# driver1.net
KiCad netlist of a schematic drawn in Altium Designer
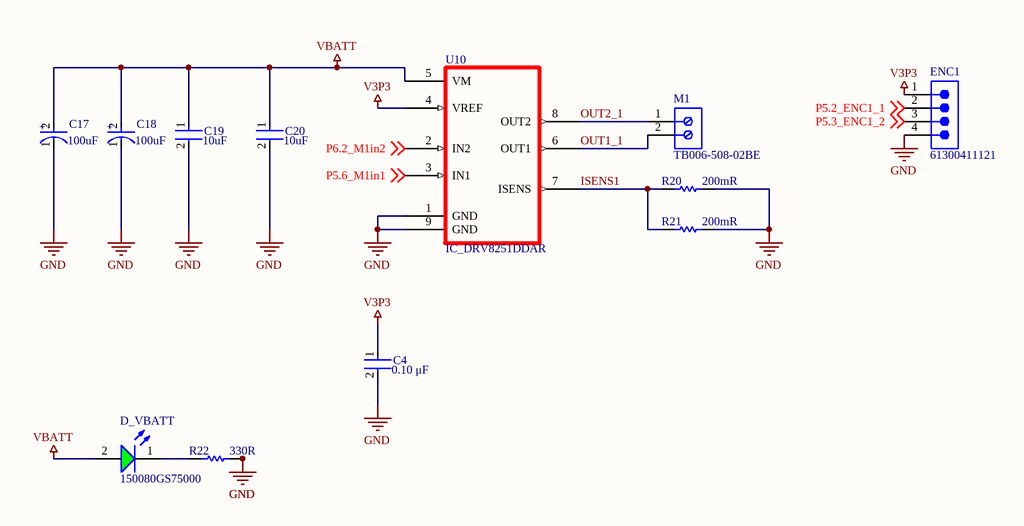
[diagram p0: driver1.SchDoc]

(export (version "E")
  (design (tool "Eeschema 10.0.6"))
  (components
    (comp (ref "C4")
      (value "C0805C104K5RACTU")
      (footprint "FP-C0805C-DN-MFG")
      (description "CAP CER 0.1UF 50V X7R 0805")
      (fields
        (field (name "MANUFACTURER") "KEMET")
        (field (name "OCTOPART") "https://octopart.com/c0805c104k5ractu-kemet-143926")
        (field (name "CAPACITANCE") "0.10 μF")
      )
      (libsource (lib "Altium Content Vault") (part "b4654b650e69147ec39a6b967a45e02"))
    )
    (comp (ref "C17")
      (value "100uF")
      (footprint "FP-SD8-MFG")
      (description "CAP ALUM 100UF 20% 25V SMD")
      (fields (field (name "VOLTAGE") "25V") (field (name "TOLERANCE") "20%"))
      (libsource (lib "Altium Content Vault") (part "a00bbbee19879c290e62620ae7e47b1"))
    )
    (comp (ref "C18")
      (value "100uF")
      (footprint "FP-SD8-MFG")
      (description "CAP ALUM 100UF 20% 25V SMD")
      (fields (field (name "VOLTAGE") "25V") (field (name "TOLERANCE") "20%"))
      (libsource (lib "Altium Content Vault") (part "a00bbbee19879c290e62620ae7e47b1"))
    )
    (comp (ref "C19")
      (value "10uF")
      (footprint "FP-C0805C-DG-MFG")
      (description "CAP CER 10UF 10V X5R 0805")
      (fields
        (field (name "MANUFACTURER") "KEMET")
        (field (name "MANUFACTURER PART NUMBER") "C0805C106K8PACTU")
      )
      (libsource (lib "Altium Content Vault") (part "11868f565c42a9108669ba33697ecf6"))
    )
    (comp (ref "C20")
      (value "10uF")
      (footprint "FP-C0805C-DG-MFG")
      (description "CAP CER 10UF 10V X5R 0805")
      (fields
        (field (name "MANUFACTURER") "KEMET")
        (field (name "MANUFACTURER PART NUMBER") "C0805C106K8PACTU")
      )
      (libsource (lib "Altium Content Vault") (part "11868f565c42a9108669ba33697ecf6"))
    )
    (comp (ref "D_VBATT")
      (value "150080GS75000")
      (footprint "WL-SMCW_0805_150080xx75000")
      (description "LED GREEN CLEAR 0805 SMD")
      (fields (field (name "MANUFACTURER") "Wurth Electronics"))
      (libsource (lib "Altium Content Vault") (part "LED_Green_2A-1K"))
    )
    (comp (ref "ENC1")
      (value "61300411121")
      (footprint "61300411121")
      (libsource (lib "Altium Content Vault") (part "Header_Male_1R_04P"))
    )
    (comp (ref "M1")
      (value "CONN_TB006_-508-02BE")
      (footprint "CUI_TB006 -508-02BE")
      (description "2~24 Poles, Screw Type, Horizontal, 5.08 Pitch, 26~14 (AWG), Terminal Block Connector")
      (fields
        (field (name "MF") "CUI Devices")
        (field (name "MP") "TB006 -508-02BE")
        (field (name "MANUFACTURER PART NUMBER") "TB006-508-02BE")
      )
      (libsource (lib "ECE453_S24") (part "CONN_TB006_-508-02BE"))
    )
    (comp (ref "R20")
      (value "200mR")
      (footprint "RESC2013X60X40LL20T25")
      (description "RES 0.2 OHM 1% 1/2W 0805")
      (fields
        (field (name "MANUFACTURER") "Panasonic")
        (field (name "MANUFACTURER PART NUMBER") "ERJ-6DSFR20V")
      )
      (libsource (lib "Altium Content Vault") (part "RES"))
    )
    (comp (ref "R21")
      (value "200mR")
      (footprint "RESC2013X60X40LL20T25")
      (description "RES 0.2 OHM 1% 1/2W 0805")
      (fields
        (field (name "MANUFACTURER") "Panasonic")
        (field (name "MANUFACTURER PART NUMBER") "ERJ-6DSFR20V")
      )
      (libsource (lib "Altium Content Vault") (part "RES"))
    )
    (comp (ref "R22")
      (value "330R")
      (footprint "RESC2013X60X40LL20T25")
      (description "RES SMD 330 OHM 1% 1/8W 0805")
      (fields
        (field (name "MANUFACTURER") "Panasonic")
        (field (name "MANUFACTURER PART NUMBER") "ERJ-6ENF3300V")
      )
      (libsource (lib "Altium Content Vault") (part "RES"))
    )
    (comp (ref "U10")
      (value "IC_DRV8251DDAR")
      (footprint "SOIC_8_PP")
      (description "48-V, 3.5-A H bridge motor driver with current regulation and latched OCP 8-SO PowerPAD -40 to 150")
      (libsource (lib "uw-madison-parts") (part "IC_DRV8251DDAR"))
    )
  )
  (nets
    (net (code "1") (name "/ISENS1") (class "Default")
      (node (ref "R20") (pin "2") (pinfunction "2_2") (pintype "passive"))
      (node (ref "R21") (pin "2") (pinfunction "2_2") (pintype "passive"))
      (node (ref "U10") (pin "7") (pinfunction "ISENS_7") (pintype "output"))
    )
    (net (code "2") (name "/OUT1_1") (class "Default")
      (node (ref "M1") (pin "2") (pinfunction "2_2") (pintype "passive"))
      (node (ref "U10") (pin "6") (pinfunction "OUT1_6") (pintype "output"))
    )
    (net (code "3") (name "/OUT2_1") (class "Default")
      (node (ref "M1") (pin "1") (pinfunction "1_1") (pintype "passive"))
      (node (ref "U10") (pin "8") (pinfunction "OUT2_8") (pintype "output"))
    )
    (net (code "4") (name "GND") (class "Default")
      (node (ref "C17") (pin "1") (pinfunction "C_1") (pintype "passive"))
      (node (ref "C18") (pin "1") (pinfunction "C_1") (pintype "passive"))
      (node (ref "C19") (pin "2") (pinfunction "2_2") (pintype "passive"))
      (node (ref "C20") (pin "2") (pinfunction "2_2") (pintype "passive"))
      (node (ref "C4") (pin "2") (pinfunction "2_2") (pintype "passive"))
      (node (ref "ENC1") (pin "4") (pinfunction "4_4") (pintype "passive"))
      (node (ref "R20") (pin "1") (pinfunction "1_1") (pintype "passive"))
      (node (ref "R21") (pin "1") (pinfunction "1_1") (pintype "passive"))
      (node (ref "R22") (pin "1") (pinfunction "1_1") (pintype "passive"))
      (node (ref "U10") (pin "1") (pinfunction "GND_1") (pintype "power_in"))
      (node (ref "U10") (pin "9") (pinfunction "GND_9") (pintype "power_in"))
    )
    (net (code "5") (name "Net-(D_VBATT-K)") (class "Default")
      (node (ref "D_VBATT") (pin "1") (pinfunction "K_1") (pintype "passive"))
      (node (ref "R22") (pin "2") (pinfunction "2_2") (pintype "passive"))
    )
    (net (code "6") (name "P5.2_ENC1_1") (class "Default")
      (node (ref "ENC1") (pin "2") (pinfunction "2_2") (pintype "passive"))
    )
    (net (code "7") (name "P5.3_ENC1_2") (class "Default")
      (node (ref "ENC1") (pin "3") (pinfunction "3_3") (pintype "passive"))
    )
    (net (code "8") (name "P5.6_M1in1") (class "Default")
      (node (ref "U10") (pin "3") (pinfunction "IN1_3") (pintype "input"))
    )
    (net (code "9") (name "P6.2_M1in2") (class "Default")
      (node (ref "U10") (pin "2") (pinfunction "IN2_2") (pintype "input"))
    )
    (net (code "10") (name "V3P3") (class "Default")
      (node (ref "C4") (pin "1") (pinfunction "1_1") (pintype "passive"))
      (node (ref "ENC1") (pin "1") (pinfunction "1_1") (pintype "passive"))
      (node (ref "U10") (pin "4") (pinfunction "VREF_4") (pintype "input"))
    )
    (net (code "11") (name "VBATT") (class "Default")
      (node (ref "C17") (pin "2") (pinfunction "A_2") (pintype "passive"))
      (node (ref "C18") (pin "2") (pinfunction "A_2") (pintype "passive"))
      (node (ref "C19") (pin "1") (pinfunction "1_1") (pintype "passive"))
      (node (ref "C20") (pin "1") (pinfunction "1_1") (pintype "passive"))
      (node (ref "D_VBATT") (pin "2") (pinfunction "A_2") (pintype "passive"))
      (node (ref "U10") (pin "5") (pinfunction "VM_5") (pintype "power_in"))
    )
  )
)
